# Oscilador.net
KiCad netlist of a schematic drawn in Altium Designer
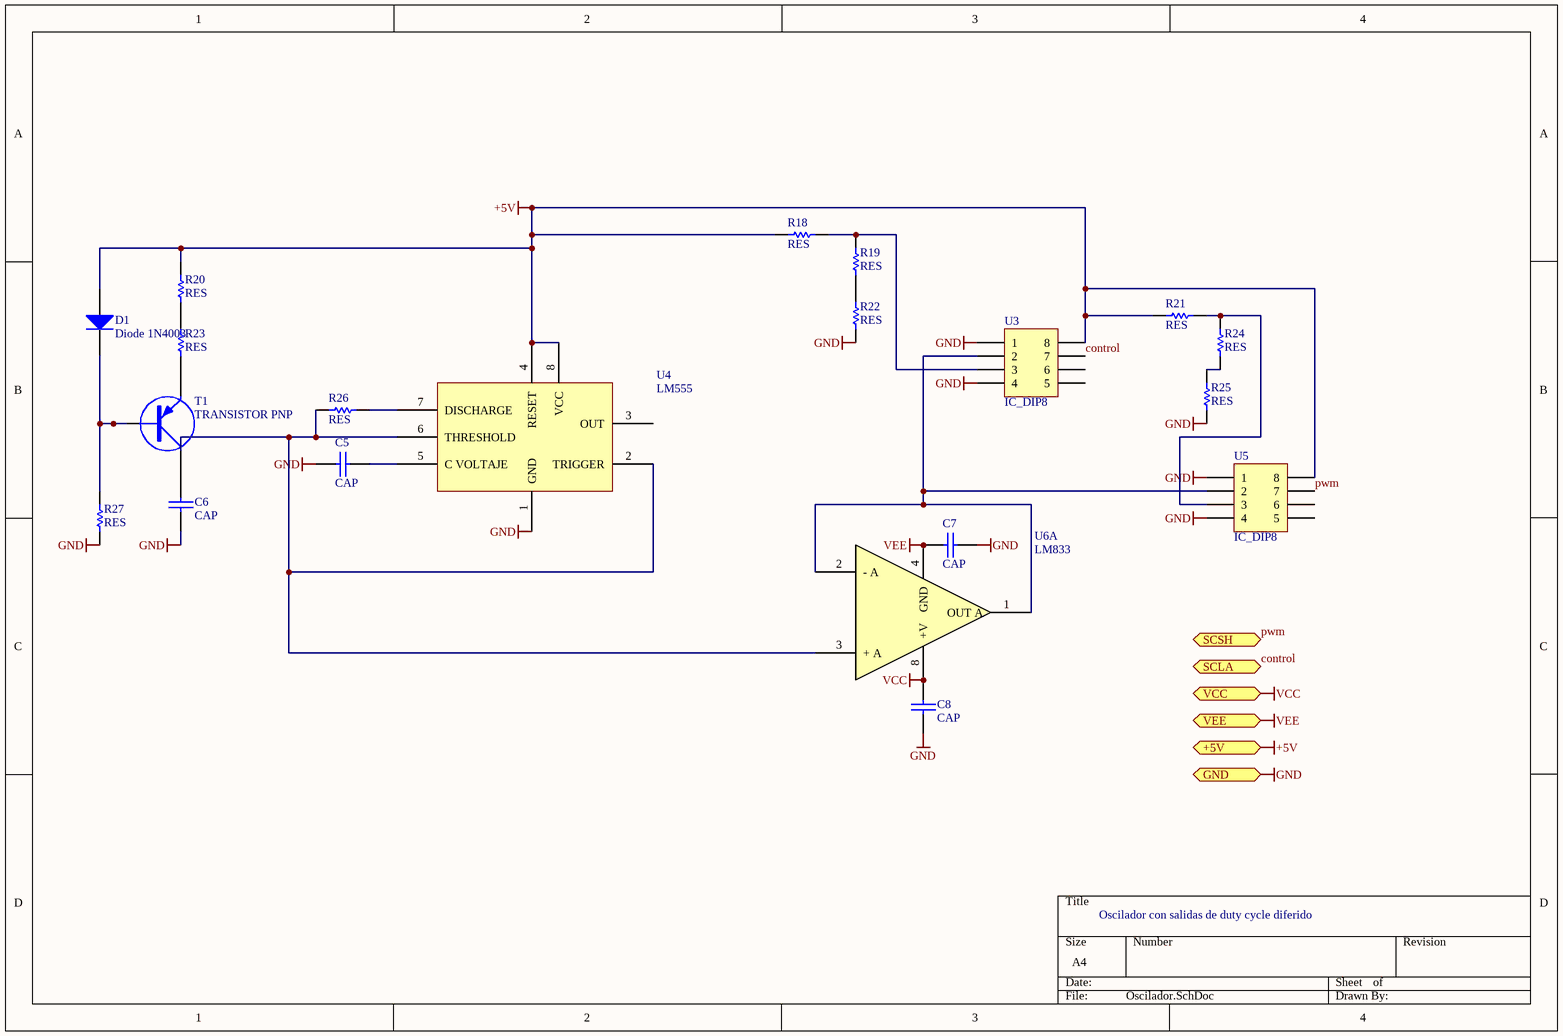
[diagram p0: Oscilador.SchDoc]

(export (version "E")
  (design (tool "Eeschema 10.0.6"))
  (components
    (comp (ref "C5") (value "CAP") (footprint "CAP100") (libsource (lib "LIBEBAL") (part "CAP")))
    (comp (ref "C6") (value "CAP") (footprint "CAP100") (libsource (lib "LIBEBAL") (part "CAP")))
    (comp (ref "C7") (value "CAP") (footprint "CAP100") (libsource (lib "LIBEBAL") (part "CAP")))
    (comp (ref "C8") (value "CAP") (footprint "CAP100") (libsource (lib "LIBEBAL") (part "CAP")))
    (comp (ref "D1")
      (value "Diode 1N4003")
      (footprint "DO-41")
      (description "1 Amp General Purpose Rectifier")
      (fields (field (name "PUBLISHER") "Altium Limited"))
      (libsource (lib "Miscellaneous Devices") (part "Diode 1N4003"))
    )
    (comp (ref "R18") (value "RES") (footprint "RES300") (libsource (lib "LIBEBAL") (part "RES")))
    (comp (ref "R19") (value "RES") (footprint "RES300") (libsource (lib "LIBEBAL") (part "RES")))
    (comp (ref "R20") (value "RES") (footprint "RES300") (libsource (lib "LIBEBAL") (part "RES")))
    (comp (ref "R21") (value "RES") (footprint "RES300") (libsource (lib "LIBEBAL") (part "RES")))
    (comp (ref "R22") (value "RES") (footprint "RES300") (libsource (lib "LIBEBAL") (part "RES")))
    (comp (ref "R23") (value "RES") (footprint "RES300") (libsource (lib "LIBEBAL") (part "RES")))
    (comp (ref "R24") (value "RES") (footprint "RES300") (libsource (lib "LIBEBAL") (part "RES")))
    (comp (ref "R25") (value "RES") (footprint "RES300") (libsource (lib "LIBEBAL") (part "RES")))
    (comp (ref "R26") (value "RES") (footprint "RES300") (libsource (lib "LIBEBAL") (part "RES")))
    (comp (ref "R27") (value "RES") (footprint "RES300") (libsource (lib "LIBEBAL") (part "RES")))
    (comp (ref "T1")
      (value "TRANSISTOR PNP")
      (footprint "TO92")
      (libsource (lib "LIBEBAL") (part "TRANSISTOR PNP"))
    )
    (comp (ref "U3") (value "IC_DIP8") (footprint "DIP8") (libsource (lib "LIBEBAL") (part "IC_DIP8")))
    (comp (ref "U4")
      (value "LM555")
      (footprint "DIP8")
      (description "Timer")
      (libsource (lib "LIBEBAL") (part "LM555"))
    )
    (comp (ref "U5") (value "IC_DIP8") (footprint "DIP8") (libsource (lib "LIBEBAL") (part "IC_DIP8")))
    (comp (ref "U6")
      (value "LM833")
      (footprint "DIP8")
      (description "Dual Audio Operational Amplifier")
      (libsource (lib "LIBEBAL") (part "LM833"))
    )
  )
  (nets
    (net (code "1") (name "+5V") (class "Default")
      (node (ref "D1") (pin "1") (pinfunction "A_1") (pintype "passive"))
      (node (ref "R18") (pin "1") (pinfunction "1_1") (pintype "passive"))
      (node (ref "R20") (pin "2") (pinfunction "2_2") (pintype "passive"))
      (node (ref "R21") (pin "1") (pinfunction "1_1") (pintype "passive"))
      (node (ref "U3") (pin "8") (pinfunction "8_8") (pintype "passive"))
      (node (ref "U4") (pin "4") (pinfunction "RESET_4") (pintype "passive"))
      (node (ref "U4") (pin "8") (pinfunction "VCC_8") (pintype "passive"))
      (node (ref "U5") (pin "8") (pinfunction "8_8") (pintype "passive"))
    )
    (net (code "2") (name "/control") (class "Default")
      (node (ref "U3") (pin "7") (pinfunction "7_7") (pintype "passive"))
    )
    (net (code "3") (name "/pwm") (class "Default")
      (node (ref "U5") (pin "7") (pinfunction "7_7") (pintype "passive"))
    )
    (net (code "4") (name "GND") (class "Default")
      (node (ref "C5") (pin "2") (pinfunction "2_2") (pintype "passive"))
      (node (ref "C6") (pin "2") (pinfunction "2_2") (pintype "passive"))
      (node (ref "C7") (pin "2") (pinfunction "2_2") (pintype "passive"))
      (node (ref "C8") (pin "2") (pinfunction "2_2") (pintype "passive"))
      (node (ref "R22") (pin "1") (pinfunction "1_1") (pintype "passive"))
      (node (ref "R25") (pin "1") (pinfunction "1_1") (pintype "passive"))
      (node (ref "R27") (pin "1") (pinfunction "1_1") (pintype "passive"))
      (node (ref "U3") (pin "1") (pinfunction "1_1") (pintype "passive"))
      (node (ref "U3") (pin "4") (pinfunction "4_4") (pintype "passive"))
      (node (ref "U4") (pin "1") (pinfunction "GND_1") (pintype "passive"))
      (node (ref "U5") (pin "1") (pinfunction "1_1") (pintype "passive"))
      (node (ref "U5") (pin "4") (pinfunction "4_4") (pintype "passive"))
    )
    (net (code "5") (name "Net-(D1-K)") (class "Default")
      (node (ref "D1") (pin "2") (pinfunction "K_2") (pintype "passive"))
      (node (ref "R27") (pin "2") (pinfunction "2_2") (pintype "passive"))
      (node (ref "T1") (pin "1") (pinfunction "B_1") (pintype "passive"))
    )
    (net (code "6") (name "Net-(R18-Pad2)") (class "Default")
      (node (ref "R18") (pin "2") (pinfunction "2_2") (pintype "passive"))
      (node (ref "R19") (pin "2") (pinfunction "2_2") (pintype "passive"))
      (node (ref "U3") (pin "3") (pinfunction "3_3") (pintype "passive"))
    )
    (net (code "7") (name "Net-(R19-Pad1)") (class "Default")
      (node (ref "R19") (pin "1") (pinfunction "1_1") (pintype "passive"))
      (node (ref "R22") (pin "2") (pinfunction "2_2") (pintype "passive"))
    )
    (net (code "8") (name "Net-(R20-Pad1)") (class "Default")
      (node (ref "R20") (pin "1") (pinfunction "1_1") (pintype "passive"))
      (node (ref "R23") (pin "2") (pinfunction "2_2") (pintype "passive"))
    )
    (net (code "9") (name "Net-(R21-Pad2)") (class "Default")
      (node (ref "R21") (pin "2") (pinfunction "2_2") (pintype "passive"))
      (node (ref "R24") (pin "2") (pinfunction "2_2") (pintype "passive"))
      (node (ref "U5") (pin "3") (pinfunction "3_3") (pintype "passive"))
    )
    (net (code "10") (name "Net-(R24-Pad1)") (class "Default")
      (node (ref "R24") (pin "1") (pinfunction "1_1") (pintype "passive"))
      (node (ref "R25") (pin "2") (pinfunction "2_2") (pintype "passive"))
    )
    (net (code "11") (name "Net-(T1-C)") (class "Default")
      (node (ref "C6") (pin "1") (pinfunction "1_1") (pintype "passive"))
      (node (ref "T1") (pin "2") (pinfunction "C_2") (pintype "passive"))
    )
    (net (code "12") (name "Net-(T1-E)") (class "Default")
      (node (ref "R23") (pin "1") (pinfunction "1_1") (pintype "passive"))
      (node (ref "T1") (pin "3") (pinfunction "E_3") (pintype "passive"))
    )
    (net (code "13") (name "Net-(U4-C_VOLTAJE)") (class "Default")
      (node (ref "C5") (pin "1") (pinfunction "1_1") (pintype "passive"))
      (node (ref "U4") (pin "5") (pinfunction "C_VOLTAJE_5") (pintype "passive"))
    )
    (net (code "14") (name "Net-(U4-DISCHARGE)") (class "Default")
      (node (ref "R26") (pin "2") (pinfunction "2_2") (pintype "passive"))
      (node (ref "U4") (pin "7") (pinfunction "DISCHARGE_7") (pintype "passive"))
    )
    (net (code "15") (name "Net-(U4-THRESHOLD)") (class "Default")
      (node (ref "R26") (pin "1") (pinfunction "1_1") (pintype "passive"))
      (node (ref "U4") (pin "2") (pinfunction "TRIGGER_2") (pintype "passive"))
      (node (ref "U4") (pin "6") (pinfunction "THRESHOLD_6") (pintype "passive"))
      (node (ref "U6") (pin "3") (pinfunction "+_A_3") (pintype "passive"))
    )
    (net (code "16") (name "Net-(U6A--_A)") (class "Default")
      (node (ref "U3") (pin "2") (pinfunction "2_2") (pintype "passive"))
      (node (ref "U5") (pin "2") (pinfunction "2_2") (pintype "passive"))
      (node (ref "U6") (pin "1") (pinfunction "OUT_A_1") (pintype "passive"))
      (node (ref "U6") (pin "2") (pinfunction "-_A_2") (pintype "passive"))
    )
    (net (code "17") (name "VCC") (class "Default")
      (node (ref "C8") (pin "1") (pinfunction "1_1") (pintype "passive"))
      (node (ref "U6") (pin "8") (pinfunction "+V_8") (pintype "passive"))
    )
    (net (code "18") (name "VEE") (class "Default")
      (node (ref "C7") (pin "1") (pinfunction "1_1") (pintype "passive"))
      (node (ref "U6") (pin "4") (pinfunction "GND_4") (pintype "passive"))
    )
    (net (code "19") (name "unconnected-(U3-Pad5)") (class "Default")
      (node (ref "U3") (pin "5") (pinfunction "5_5") (pintype "passive"))
    )
    (net (code "20") (name "unconnected-(U3-Pad6)") (class "Default")
      (node (ref "U3") (pin "6") (pinfunction "6_6") (pintype "passive"))
    )
    (net (code "21") (name "unconnected-(U4-OUT-Pad3)") (class "Default")
      (node (ref "U4") (pin "3") (pinfunction "OUT_3") (pintype "passive"))
    )
    (net (code "22") (name "unconnected-(U5-Pad5)") (class "Default")
      (node (ref "U5") (pin "5") (pinfunction "5_5") (pintype "passive"))
    )
    (net (code "23") (name "unconnected-(U5-Pad6)") (class "Default")
      (node (ref "U5") (pin "6") (pinfunction "6_6") (pintype "passive"))
    )
  )
)
